# design.net
KiCad netlist of a schematic drawn in Altium Designer
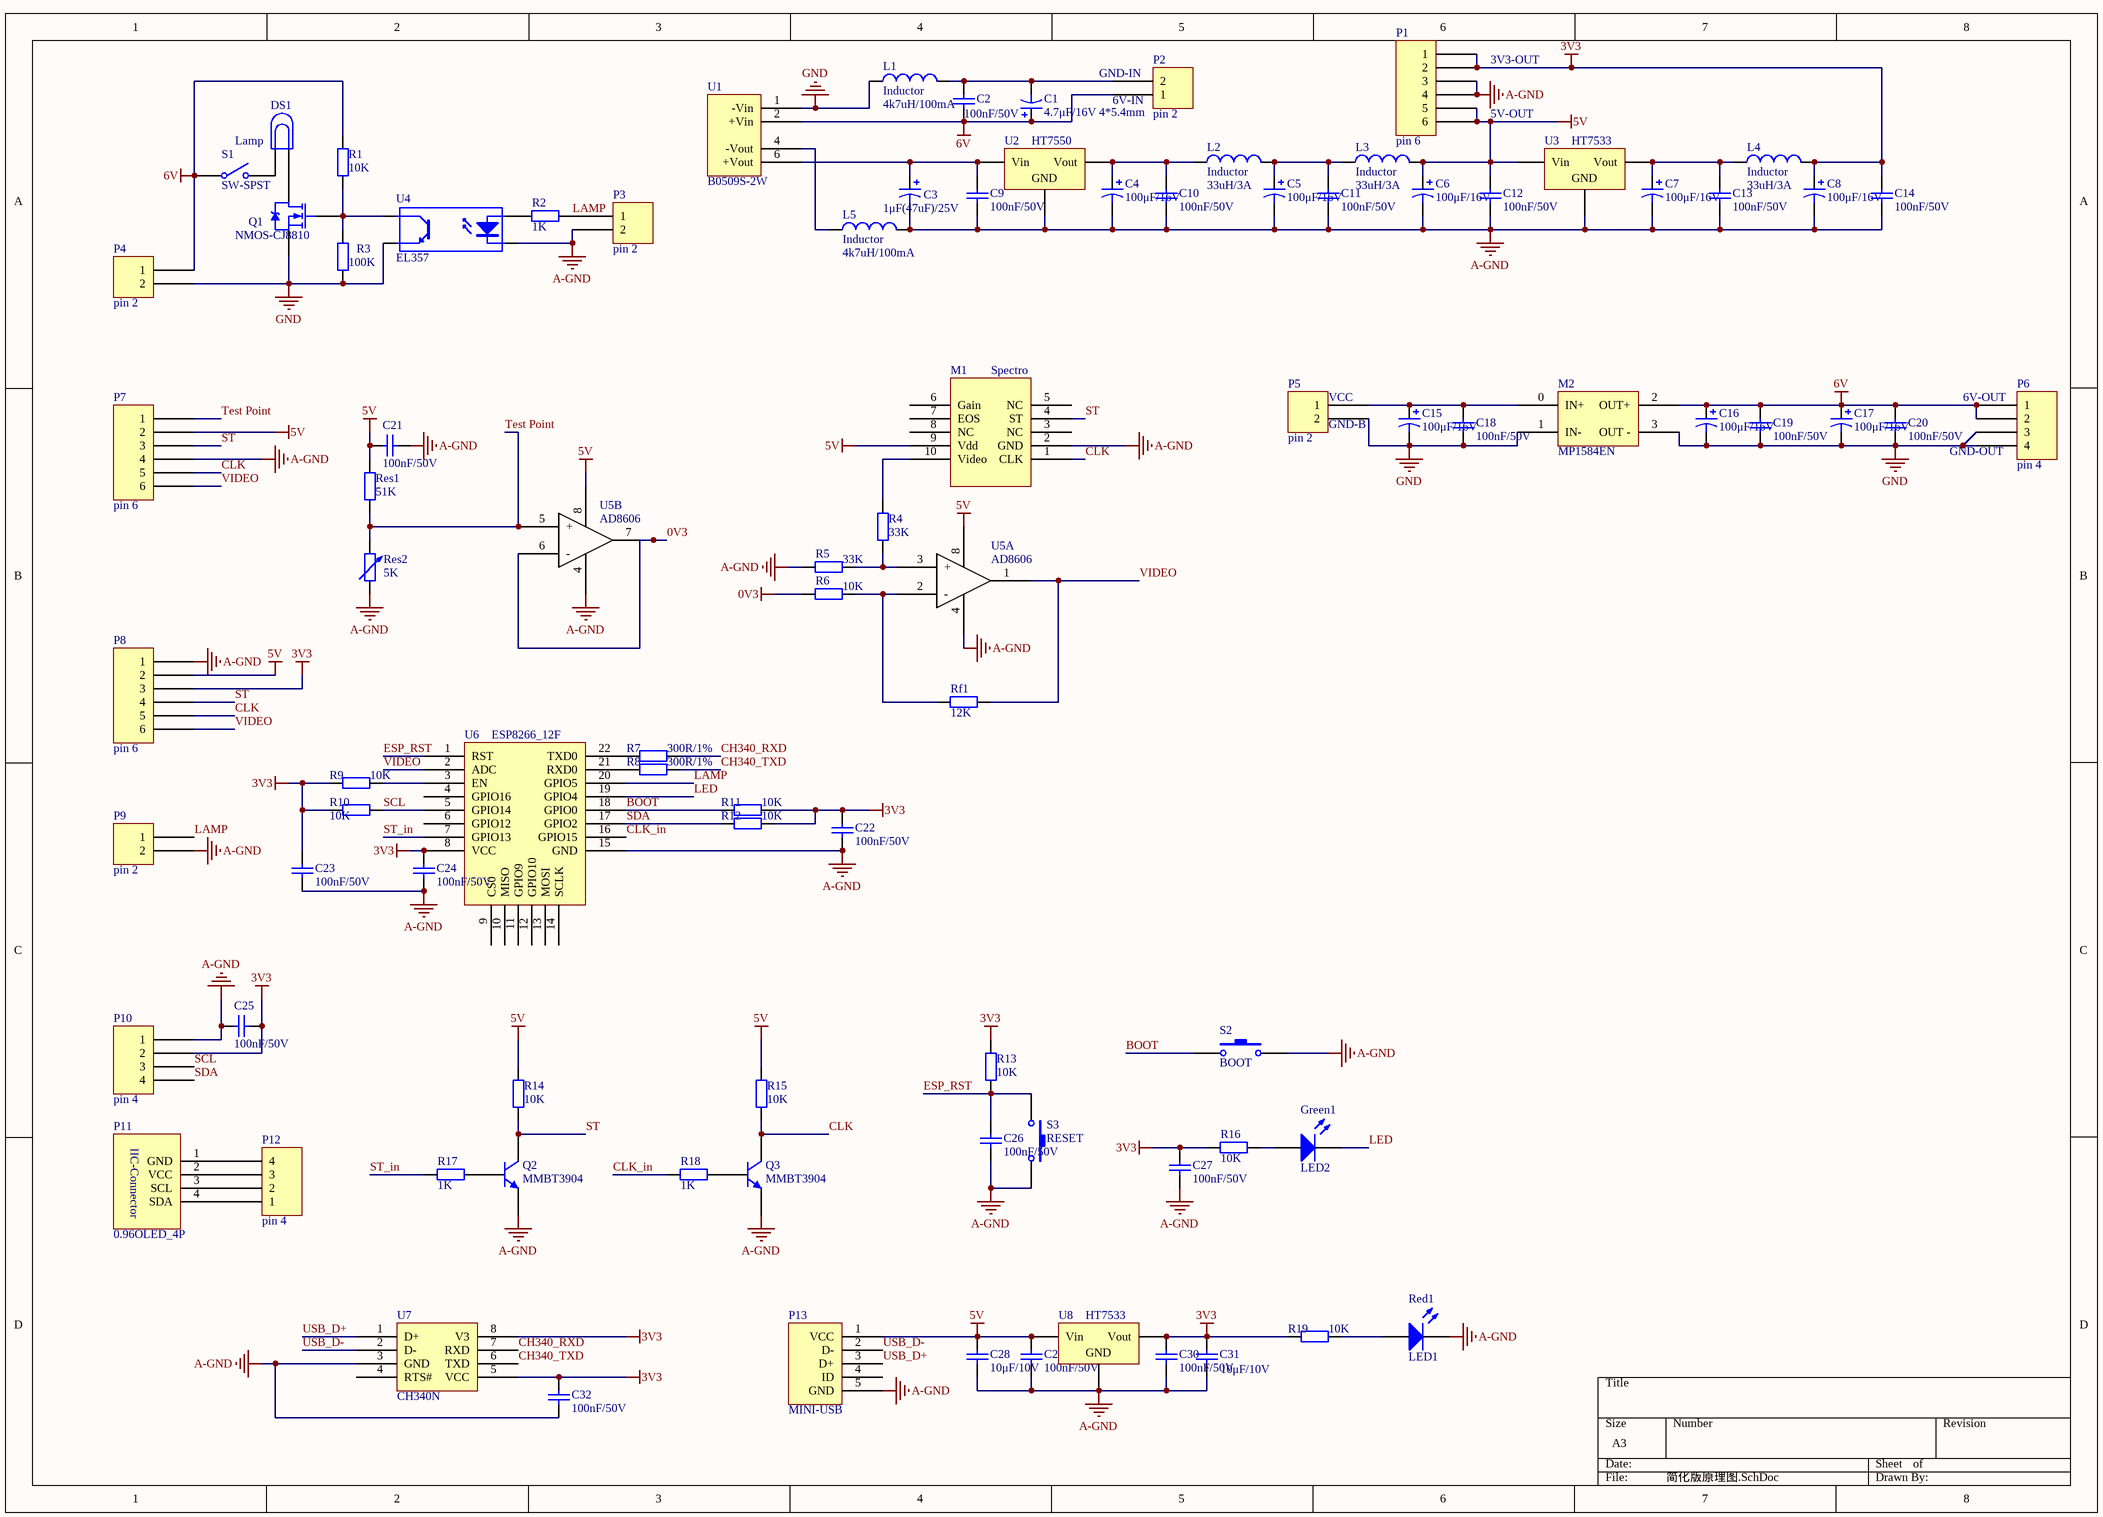
[diagram p0: 简化版原理图.SchDoc]

(export (version "E")
  (design (tool "Eeschema 10.0.6"))
  (components
    (comp (ref "C1")
      (value "4.7μF/16V 4*5.4mm")
      (footprint "CAP4x5.4-SMD")
      (description "Polarized Capacitor (Radial)")
      (fields (field (name "PUBLISHER") "Altium Limited"))
      (libsource (lib "Miscellaneous Devices") (part "Cap Pol1"))
    )
    (comp (ref "C2")
      (value "100nF/50V")
      (footprint "0603")
      (description "Capacitor")
      (fields (field (name "PUBLISHER") "Altium Limited"))
      (libsource (lib "Miscellaneous Devices") (part "Cap"))
    )
    (comp (ref "C3")
      (value "1μF(47uF)/25V")
      (footprint "CAP6.3x5.4-SMD")
      (description "Polarized Capacitor (Radial)")
      (fields (field (name "PUBLISHER") "Altium Limited"))
      (libsource (lib "Miscellaneous Devices") (part "Cap Pol1"))
    )
    (comp (ref "C4")
      (value "100μF/16V")
      (footprint "CAP6.3x5.4-SMD")
      (description "Polarized Capacitor (Radial)")
      (fields (field (name "PUBLISHER") "Altium Limited"))
      (libsource (lib "Miscellaneous Devices") (part "Cap Pol1"))
    )
    (comp (ref "C5")
      (value "100μF/16V")
      (footprint "CAP6.3x5.4-SMD")
      (description "Polarized Capacitor (Radial)")
      (fields (field (name "PUBLISHER") "Altium Limited"))
      (libsource (lib "Miscellaneous Devices") (part "Cap Pol1"))
    )
    (comp (ref "C6")
      (value "100μF/16V")
      (footprint "CAP6.3x5.4-SMD")
      (description "Polarized Capacitor (Radial)")
      (fields (field (name "PUBLISHER") "Altium Limited"))
      (libsource (lib "Miscellaneous Devices") (part "Cap Pol1"))
    )
    (comp (ref "C7")
      (value "100μF/16V")
      (footprint "CAP6.3x5.4-SMD")
      (description "Polarized Capacitor (Radial)")
      (fields (field (name "PUBLISHER") "Altium Limited"))
      (libsource (lib "Miscellaneous Devices") (part "Cap Pol1"))
    )
    (comp (ref "C8")
      (value "100μF/16V")
      (footprint "CAP6.3x5.4-SMD")
      (description "Polarized Capacitor (Radial)")
      (fields (field (name "PUBLISHER") "Altium Limited"))
      (libsource (lib "Miscellaneous Devices") (part "Cap Pol1"))
    )
    (comp (ref "C9")
      (value "100nF/50V")
      (footprint "0603")
      (description "Capacitor")
      (fields (field (name "PUBLISHER") "Altium Limited"))
      (libsource (lib "Miscellaneous Devices") (part "Cap"))
    )
    (comp (ref "C10")
      (value "100nF/50V")
      (footprint "0603")
      (description "Capacitor")
      (fields (field (name "PUBLISHER") "Altium Limited"))
      (libsource (lib "Miscellaneous Devices") (part "Cap"))
    )
    (comp (ref "C11")
      (value "100nF/50V")
      (footprint "0603")
      (description "Capacitor")
      (fields (field (name "PUBLISHER") "Altium Limited"))
      (libsource (lib "Miscellaneous Devices") (part "Cap"))
    )
    (comp (ref "C12")
      (value "100nF/50V")
      (footprint "0603")
      (description "Capacitor")
      (fields (field (name "PUBLISHER") "Altium Limited"))
      (libsource (lib "Miscellaneous Devices") (part "Cap"))
    )
    (comp (ref "C13")
      (value "100nF/50V")
      (footprint "0603")
      (description "Capacitor")
      (fields (field (name "PUBLISHER") "Altium Limited"))
      (libsource (lib "Miscellaneous Devices") (part "Cap"))
    )
    (comp (ref "C14")
      (value "100nF/50V")
      (footprint "0603")
      (description "Capacitor")
      (fields (field (name "PUBLISHER") "Altium Limited"))
      (libsource (lib "Miscellaneous Devices") (part "Cap"))
    )
    (comp (ref "C15")
      (value "100μF/16V")
      (footprint "CAP6.3x5.4-SMD")
      (description "Polarized Capacitor (Radial)")
      (fields (field (name "PUBLISHER") "Altium Limited"))
      (libsource (lib "Miscellaneous Devices") (part "Cap Pol1"))
    )
    (comp (ref "C16")
      (value "100μF/16V")
      (footprint "CAP6.3x5.4-SMD")
      (description "Polarized Capacitor (Radial)")
      (fields (field (name "PUBLISHER") "Altium Limited"))
      (libsource (lib "Miscellaneous Devices") (part "Cap Pol1"))
    )
    (comp (ref "C17")
      (value "100μF/16V")
      (footprint "CAP6.3x5.4-SMD")
      (description "Polarized Capacitor (Radial)")
      (fields (field (name "PUBLISHER") "Altium Limited"))
      (libsource (lib "Miscellaneous Devices") (part "Cap Pol1"))
    )
    (comp (ref "C18")
      (value "100nF/50V")
      (footprint "0603")
      (description "Capacitor")
      (fields (field (name "PUBLISHER") "Altium Limited"))
      (libsource (lib "Miscellaneous Devices") (part "Cap"))
    )
    (comp (ref "C19")
      (value "100nF/50V")
      (footprint "0603")
      (description "Capacitor")
      (fields (field (name "PUBLISHER") "Altium Limited"))
      (libsource (lib "Miscellaneous Devices") (part "Cap"))
    )
    (comp (ref "C20")
      (value "100nF/50V")
      (footprint "0603")
      (description "Capacitor")
      (fields (field (name "PUBLISHER") "Altium Limited"))
      (libsource (lib "Miscellaneous Devices") (part "Cap"))
    )
    (comp (ref "C21")
      (value "100nF/50V")
      (footprint "0603")
      (description "Capacitor")
      (fields (field (name "PUBLISHER") "Altium Limited"))
      (libsource (lib "Miscellaneous Devices") (part "Cap"))
    )
    (comp (ref "C22")
      (value "100nF/50V")
      (footprint "0603")
      (description "Capacitor")
      (fields (field (name "PUBLISHER") "Altium Limited"))
      (libsource (lib "Miscellaneous Devices") (part "Cap"))
    )
    (comp (ref "C23")
      (value "100nF/50V")
      (footprint "0603")
      (description "Capacitor")
      (fields (field (name "PUBLISHER") "Altium Limited"))
      (libsource (lib "Miscellaneous Devices") (part "Cap"))
    )
    (comp (ref "C24")
      (value "100nF/50V")
      (footprint "0603")
      (description "Capacitor")
      (fields (field (name "PUBLISHER") "Altium Limited"))
      (libsource (lib "Miscellaneous Devices") (part "Cap"))
    )
    (comp (ref "C25")
      (value "100nF/50V")
      (footprint "0603")
      (description "Capacitor")
      (fields (field (name "PUBLISHER") "Altium Limited"))
      (libsource (lib "Miscellaneous Devices") (part "Cap"))
    )
    (comp (ref "C26")
      (value "100nF/50V")
      (footprint "0603")
      (description "Capacitor")
      (fields (field (name "PUBLISHER") "Altium Limited"))
      (libsource (lib "Miscellaneous Devices") (part "Cap"))
    )
    (comp (ref "C27")
      (value "100nF/50V")
      (footprint "0603")
      (description "Capacitor")
      (fields (field (name "PUBLISHER") "Altium Limited"))
      (libsource (lib "Miscellaneous Devices") (part "Cap"))
    )
    (comp (ref "C28")
      (value "10μF/10V")
      (footprint "0805")
      (description "Capacitor")
      (fields (field (name "PUBLISHER") "Altium Limited"))
      (libsource (lib "Miscellaneous Devices") (part "Cap"))
    )
    (comp (ref "C29")
      (value "100nF/50V")
      (footprint "0603")
      (description "Capacitor")
      (fields (field (name "PUBLISHER") "Altium Limited"))
      (libsource (lib "Miscellaneous Devices") (part "Cap"))
    )
    (comp (ref "C30")
      (value "100nF/50V")
      (footprint "0603")
      (description "Capacitor")
      (fields (field (name "PUBLISHER") "Altium Limited"))
      (libsource (lib "Miscellaneous Devices") (part "Cap"))
    )
    (comp (ref "C31")
      (value "10μF/10V")
      (footprint "0805")
      (description "Capacitor")
      (fields (field (name "PUBLISHER") "Altium Limited"))
      (libsource (lib "Miscellaneous Devices") (part "Cap"))
    )
    (comp (ref "C32")
      (value "100nF/50V")
      (footprint "0603")
      (description "Capacitor")
      (fields (field (name "PUBLISHER") "Altium Limited"))
      (libsource (lib "Miscellaneous Devices") (part "Cap"))
    )
    (comp (ref "DS1")
      (value "Lamp")
      (footprint "LAMP")
      (description "Incandescent Bulb")
      (fields (field (name "PUBLISHER") "Altium Limited"))
      (libsource (lib "Miscellaneous Devices") (part "Lamp"))
    )
    (comp (ref "Green1")
      (value "LED2")
      (footprint "0805-LED")
      (description "Typical RED GaAs LED")
      (fields (field (name "PUBLISHER") "Altium Limited"))
      (libsource (lib "Miscellaneous Devices") (part "LED1"))
    )
    (comp (ref "L1")
      (value "Inductor")
      (footprint "L 0810")
      (fields (field (name "ALTIUM_VALUE") "4k7uH/100mA") (field (name "PUBLISHER") "Altium Limited"))
      (libsource (lib "Miscellaneous Devices") (part "Inductor"))
    )
    (comp (ref "L2")
      (value "Inductor")
      (footprint "0650")
      (fields (field (name "ALTIUM_VALUE") "33uH/3A") (field (name "PUBLISHER") "Altium Limited"))
      (libsource (lib "Miscellaneous Devices") (part "Inductor"))
    )
    (comp (ref "L3")
      (value "Inductor")
      (footprint "0650")
      (fields (field (name "ALTIUM_VALUE") "33uH/3A") (field (name "PUBLISHER") "Altium Limited"))
      (libsource (lib "Miscellaneous Devices") (part "Inductor"))
    )
    (comp (ref "L4")
      (value "Inductor")
      (footprint "0650")
      (fields (field (name "ALTIUM_VALUE") "33uH/3A") (field (name "PUBLISHER") "Altium Limited"))
      (libsource (lib "Miscellaneous Devices") (part "Inductor"))
    )
    (comp (ref "L5")
      (value "Inductor")
      (footprint "L 0810")
      (fields (field (name "ALTIUM_VALUE") "4k7uH/100mA") (field (name "PUBLISHER") "Altium Limited"))
      (libsource (lib "Miscellaneous Devices") (part "Inductor"))
    )
    (comp (ref "M1") (value "Spectro") (footprint "c10988ma") (libsource (lib "第一版SCH库") (part "Spectro")))
    (comp (ref "M2")
      (value "MP1584EN")
      (footprint "MP1584EN模块")
      (libsource (lib "简化版PCB") (part "MP1584EN模块"))
    )
    (comp (ref "P1") (value "pin 6") (footprint "PIN-6-2.54-1.0") (libsource (lib "简化版PCB") (part "pin 6")))
    (comp (ref "P2") (value "pin 2") (footprint "PIN-2-2.54-1.0") (libsource (lib "") (part "pin 2_2")))
    (comp (ref "P3") (value "pin 2") (footprint "PIN-2-2.54-1.0") (libsource (lib "简化版PCB") (part "pin 2")))
    (comp (ref "P4") (value "pin 2") (footprint "PIN-2-2.54-1.0") (libsource (lib "") (part "pin 2_1")))
    (comp (ref "P5") (value "pin 2") (footprint "PIN-2-2.54-1.0") (libsource (lib "") (part "pin 2_1")))
    (comp (ref "P6") (value "pin 4") (footprint "PIN-4-2.54-1.0") (libsource (lib "") (part "pin 4_2")))
    (comp (ref "P7") (value "pin 6") (footprint "PIN-6-2.54-1.0") (libsource (lib "简化版PCB") (part "pin 6")))
    (comp (ref "P8") (value "pin 6") (footprint "PIN-6-2.54-1.0") (libsource (lib "简化版PCB") (part "pin 6")))
    (comp (ref "P9") (value "pin 2") (footprint "PIN-2-2.54-1.0") (libsource (lib "") (part "pin 2_1")))
    (comp (ref "P10") (value "pin 4") (footprint "PIN-4-2.54-1.0") (libsource (lib "") (part "pin 4_1")))
    (comp (ref "P11")
      (value "0.96OLED_4P")
      (footprint "OLED0.96-4P")
      (libsource (lib "第一版SCH库") (part "0.96OLED_4P"))
    )
    (comp (ref "P12") (value "pin 4") (footprint "PIN-4-2.54-1.0") (libsource (lib "简化版PCB") (part "pin 4")))
    (comp (ref "P13")
      (value "MINI-USB")
      (footprint "Micro_USB全贴片")
      (libsource (lib "第一版SCH库") (part "MINI-USB_JX"))
    )
    (comp (ref "Q1")
      (value "NMOS-CJ8810")
      (footprint "SOT-23")
      (description "N-Channel Power MOSFET")
      (fields (field (name "PUBLISHER") "Altium Limited"))
      (libsource (lib "简化版PCB") (part "NMOS-2"))
    )
    (comp (ref "Q2")
      (value "MMBT3904")
      (footprint "SOT-23")
      (description "NPN General Purpose Amplifier")
      (fields (field (name "PUBLISHER") "Altium Limited"))
      (libsource (lib "简化版PCB") (part "2N3904"))
    )
    (comp (ref "Q3")
      (value "MMBT3904")
      (footprint "SOT-23")
      (description "NPN General Purpose Amplifier")
      (fields (field (name "PUBLISHER") "Altium Limited"))
      (libsource (lib "简化版PCB") (part "2N3904"))
    )
    (comp (ref "R1")
      (value "10K")
      (footprint "0603")
      (description "Resistor")
      (fields (field (name "PUBLISHER") "Altium Limited"))
      (libsource (lib "") (part "Res2_1"))
    )
    (comp (ref "R2")
      (value "1K")
      (footprint "0603")
      (description "Resistor")
      (fields (field (name "PUBLISHER") "Altium Limited"))
      (libsource (lib "Miscellaneous Devices") (part "Res2"))
    )
    (comp (ref "R3")
      (value "100K")
      (footprint "0603")
      (description "Resistor")
      (fields (field (name "PUBLISHER") "Altium Limited"))
      (libsource (lib "") (part "Res2_1"))
    )
    (comp (ref "R4")
      (value "33K")
      (footprint "0603")
      (description "Resistor")
      (fields (field (name "PUBLISHER") "Altium Limited"))
      (libsource (lib "") (part "Res2_1"))
    )
    (comp (ref "R5")
      (value "33K")
      (footprint "0603")
      (description "Resistor")
      (fields (field (name "PUBLISHER") "Altium Limited"))
      (libsource (lib "Miscellaneous Devices") (part "Res2"))
    )
    (comp (ref "R6")
      (value "10K")
      (footprint "0603")
      (description "Resistor")
      (fields (field (name "PUBLISHER") "Altium Limited"))
      (libsource (lib "Miscellaneous Devices") (part "Res2"))
    )
    (comp (ref "R7")
      (value "300R/1%")
      (footprint "0603")
      (description "Resistor")
      (fields (field (name "PUBLISHER") "Altium Limited"))
      (libsource (lib "Miscellaneous Devices") (part "Res2"))
    )
    (comp (ref "R8")
      (value "300R/1%")
      (footprint "0603")
      (description "Resistor")
      (fields (field (name "PUBLISHER") "Altium Limited"))
      (libsource (lib "Miscellaneous Devices") (part "Res2"))
    )
    (comp (ref "R9")
      (value "10K")
      (footprint "0603")
      (description "Resistor")
      (fields (field (name "PUBLISHER") "Altium Limited"))
      (libsource (lib "Miscellaneous Devices") (part "Res2"))
    )
    (comp (ref "R10")
      (value "10K")
      (footprint "0603")
      (description "Resistor")
      (fields (field (name "PUBLISHER") "Altium Limited"))
      (libsource (lib "Miscellaneous Devices") (part "Res2"))
    )
    (comp (ref "R11")
      (value "10K")
      (footprint "0603")
      (description "Resistor")
      (fields (field (name "PUBLISHER") "Altium Limited"))
      (libsource (lib "Miscellaneous Devices") (part "Res2"))
    )
    (comp (ref "R12")
      (value "10K")
      (footprint "0603")
      (description "Resistor")
      (fields (field (name "PUBLISHER") "Altium Limited"))
      (libsource (lib "Miscellaneous Devices") (part "Res2"))
    )
    (comp (ref "R13")
      (value "10K")
      (footprint "0603")
      (description "Resistor")
      (fields (field (name "PUBLISHER") "Altium Limited"))
      (libsource (lib "") (part "Res2_1"))
    )
    (comp (ref "R14")
      (value "10K")
      (footprint "0603")
      (description "Resistor")
      (fields (field (name "PUBLISHER") "Altium Limited"))
      (libsource (lib "") (part "Res2_1"))
    )
    (comp (ref "R15")
      (value "10K")
      (footprint "0603")
      (description "Resistor")
      (fields (field (name "PUBLISHER") "Altium Limited"))
      (libsource (lib "") (part "Res2_1"))
    )
    (comp (ref "R16")
      (value "10K")
      (footprint "0603")
      (description "Resistor")
      (fields (field (name "PUBLISHER") "Altium Limited"))
      (libsource (lib "") (part "Res2_2"))
    )
    (comp (ref "R17")
      (value "1K")
      (footprint "0603")
      (description "Resistor")
      (fields (field (name "PUBLISHER") "Altium Limited"))
      (libsource (lib "") (part "Res2_2"))
    )
    (comp (ref "R18")
      (value "1K")
      (footprint "0603")
      (description "Resistor")
      (fields (field (name "PUBLISHER") "Altium Limited"))
      (libsource (lib "") (part "Res2_2"))
    )
    (comp (ref "R19")
      (value "10K")
      (footprint "0603")
      (description "Resistor")
      (fields (field (name "PUBLISHER") "Altium Limited"))
      (libsource (lib "Miscellaneous Devices") (part "Res2"))
    )
    (comp (ref "Red1")
      (value "LED1")
      (footprint "0805-LED")
      (description "Typical RED GaAs LED")
      (fields (field (name "PUBLISHER") "Altium Limited"))
      (libsource (lib "Miscellaneous Devices") (part "LED1"))
    )
    (comp (ref "Res1")
      (value "51K")
      (footprint "0603")
      (description "Resistor")
      (fields (field (name "PUBLISHER") "Altium Limited"))
      (libsource (lib "") (part "Res2_1"))
    )
    (comp (ref "Res2")
      (value "5K")
      (footprint "RES-ADJ")
      (description "Variable Resistor")
      (fields (field (name "PUBLISHER") "Altium Limited"))
      (libsource (lib "Miscellaneous Devices") (part "Res Adj2"))
    )
    (comp (ref "Rf1")
      (value "12K")
      (footprint "0603")
      (description "Resistor")
      (fields (field (name "PUBLISHER") "Altium Limited"))
      (libsource (lib "Miscellaneous Devices") (part "Res2"))
    )
    (comp (ref "S1")
      (value "SW-SPST")
      (footprint "swich-big")
      (description "Single-Pole, Single-Throw Switch")
      (fields (field (name "PUBLISHER") "Altium Limited"))
      (libsource (lib "Miscellaneous Devices") (part "SW-SPST"))
    )
    (comp (ref "S2")
      (value "BOOT")
      (footprint "Swich-mini")
      (description "Switch")
      (fields (field (name "PUBLISHER") "Altium Limited"))
      (libsource (lib "Miscellaneous Devices") (part "SW-PB"))
    )
    (comp (ref "S3")
      (value "RESET")
      (footprint "Swich-mini")
      (description "Switch")
      (fields (field (name "PUBLISHER") "Altium Limited"))
      (libsource (lib "Miscellaneous Devices") (part "SW-PB"))
    )
    (comp (ref "U1")
      (value "B0509S-2W")
      (footprint "B0509S-2W")
      (libsource (lib "第一版SCH库") (part "B0509S-2W"))
    )
    (comp (ref "U2")
      (value "HT7550")
      (footprint "SOT-89")
      (description "Voltage Regulator")
      (fields (field (name "PUBLISHER") "Altium Limited"))
      (libsource (lib "简化版PCB") (part "Volt Reg"))
    )
    (comp (ref "U3")
      (value "HT7533")
      (footprint "SOT-89")
      (description "Voltage Regulator")
      (fields (field (name "PUBLISHER") "Altium Limited"))
      (libsource (lib "简化版PCB") (part "Volt Reg"))
    )
    (comp (ref "U4")
      (value "EL357")
      (footprint "SOP4-bigger")
      (description "4-Pin Phototransistor Optocoupler")
      (fields (field (name "PUBLISHER") "Altium Limited"))
      (libsource (lib "Miscellaneous Devices") (part "Optoisolator1"))
    )
    (comp (ref "U5") (value "AD8606") (footprint "SOP8") (libsource (lib "第一版SCH库") (part "LM358")))
    (comp (ref "U6")
      (value "ESP8266_12F")
      (footprint "esp8266-12f")
      (libsource (lib "第一版SCH库") (part "ESP8266_12F"))
    )
    (comp (ref "U7") (value "CH340N") (footprint "SOP8") (libsource (lib "简化版PCB") (part "CH340N")))
    (comp (ref "U8")
      (value "HT7533")
      (footprint "SOT-89")
      (description "Voltage Regulator")
      (fields (field (name "PUBLISHER") "Altium Limited"))
      (libsource (lib "简化版PCB") (part "Volt Reg"))
    )
  )
  (nets
    (net (code "1") (name "/BOOT") (class "Default")
      (node (ref "R11") (pin "1") (pinfunction "1_1") (pintype "passive"))
      (node (ref "S2") (pin "1") (pinfunction "1_1") (pintype "passive"))
      (node (ref "U6") (pin "18") (pinfunction "GPIO0_18") (pintype "passive"))
    )
    (net (code "2") (name "/CH340_RXD") (class "Default")
      (node (ref "R7") (pin "2") (pinfunction "2_2") (pintype "passive"))
      (node (ref "U7") (pin "7") (pinfunction "RXD_7") (pintype "passive"))
    )
    (net (code "3") (name "/CH340_TXD") (class "Default")
      (node (ref "R8") (pin "2") (pinfunction "2_2") (pintype "passive"))
      (node (ref "U7") (pin "6") (pinfunction "TXD_6") (pintype "passive"))
    )
    (net (code "4") (name "/CLK") (class "Default")
      (node (ref "M1") (pin "1") (pinfunction "CLK_1") (pintype "passive"))
      (node (ref "P7") (pin "5") (pinfunction "5_5") (pintype "passive"))
      (node (ref "P8") (pin "5") (pinfunction "5_5") (pintype "passive"))
      (node (ref "Q3") (pin "3") (pinfunction "C_3") (pintype "passive"))
      (node (ref "R15") (pin "1") (pinfunction "1_1") (pintype "passive"))
    )
    (net (code "5") (name "/CLK_in") (class "Default")
      (node (ref "R18") (pin "2") (pinfunction "2_2") (pintype "passive"))
      (node (ref "U6") (pin "16") (pinfunction "GPIO15_16") (pintype "passive"))
    )
    (net (code "6") (name "/ESP_RST") (class "Default")
      (node (ref "C26") (pin "2") (pinfunction "2_2") (pintype "passive"))
      (node (ref "R13") (pin "1") (pinfunction "1_1") (pintype "passive"))
      (node (ref "S3") (pin "1") (pinfunction "1_1") (pintype "passive"))
      (node (ref "U6") (pin "1") (pinfunction "RST_1") (pintype "passive"))
    )
    (net (code "7") (name "/LAMP") (class "Default")
      (node (ref "P3") (pin "1") (pinfunction "1_1") (pintype "passive"))
      (node (ref "P9") (pin "1") (pinfunction "1_1") (pintype "passive"))
      (node (ref "R2") (pin "2") (pinfunction "2_2") (pintype "passive"))
      (node (ref "U6") (pin "20") (pinfunction "GPIO5_20") (pintype "passive"))
    )
    (net (code "8") (name "/LED") (class "Default")
      (node (ref "Green1") (pin "2") (pinfunction "K_2") (pintype "passive"))
      (node (ref "U6") (pin "19") (pinfunction "GPIO4_19") (pintype "passive"))
    )
    (net (code "9") (name "/SCL") (class "Default")
      (node (ref "P10") (pin "3") (pinfunction "3_3") (pintype "passive"))
      (node (ref "R10") (pin "2") (pinfunction "2_2") (pintype "passive"))
      (node (ref "U6") (pin "5") (pinfunction "GPIO14_5") (pintype "passive"))
    )
    (net (code "10") (name "/SDA") (class "Default")
      (node (ref "P10") (pin "4") (pinfunction "4_4") (pintype "passive"))
      (node (ref "R12") (pin "1") (pinfunction "1_1") (pintype "passive"))
      (node (ref "U6") (pin "17") (pinfunction "GPIO2_17") (pintype "passive"))
    )
    (net (code "11") (name "/ST") (class "Default")
      (node (ref "M1") (pin "4") (pinfunction "ST_4") (pintype "passive"))
      (node (ref "P7") (pin "3") (pinfunction "3_3") (pintype "passive"))
      (node (ref "P8") (pin "4") (pinfunction "4_4") (pintype "passive"))
      (node (ref "Q2") (pin "3") (pinfunction "C_3") (pintype "passive"))
      (node (ref "R14") (pin "1") (pinfunction "1_1") (pintype "passive"))
    )
    (net (code "12") (name "/ST_in") (class "Default")
      (node (ref "R17") (pin "2") (pinfunction "2_2") (pintype "passive"))
      (node (ref "U6") (pin "7") (pinfunction "GPIO13_7") (pintype "passive"))
    )
    (net (code "13") (name "/Test Point") (class "Default")
      (node (ref "P7") (pin "1") (pinfunction "1_1") (pintype "passive"))
      (node (ref "Res1") (pin "1") (pinfunction "1_1") (pintype "passive"))
      (node (ref "Res2") (pin "2") (pinfunction "2_2") (pintype "passive"))
      (node (ref "U5") (pin "5") (pinfunction "+_5") (pintype "passive"))
    )
    (net (code "14") (name "/USB_D+") (class "Default")
      (node (ref "P13") (pin "3") (pinfunction "D+_3") (pintype "passive"))
      (node (ref "U7") (pin "1") (pinfunction "D+_1") (pintype "passive"))
    )
    (net (code "15") (name "/USB_D-") (class "Default")
      (node (ref "P13") (pin "2") (pinfunction "D-_2") (pintype "passive"))
      (node (ref "U7") (pin "2") (pinfunction "D-_2") (pintype "passive"))
    )
    (net (code "16") (name "/VIDEO") (class "Default")
      (node (ref "P7") (pin "6") (pinfunction "6_6") (pintype "passive"))
      (node (ref "P8") (pin "6") (pinfunction "6_6") (pintype "passive"))
      (node (ref "Rf1") (pin "2") (pinfunction "2_2") (pintype "passive"))
      (node (ref "U5") (pin "1") (pinfunction "OUT_1") (pintype "passive"))
      (node (ref "U6") (pin "2") (pinfunction "ADC_2") (pintype "passive"))
    )
    (net (code "17") (name "0V3") (class "Default")
      (node (ref "R6") (pin "1") (pinfunction "1_1") (pintype "passive"))
      (node (ref "U5") (pin "6") (pinfunction "-_6") (pintype "passive"))
      (node (ref "U5") (pin "7") (pinfunction "OUT_7") (pintype "passive"))
    )
    (net (code "18") (name "3V3") (class "Default")
      (node (ref "C14") (pin "2") (pinfunction "2_2") (pintype "passive"))
      (node (ref "C22") (pin "2") (pinfunction "2_2") (pintype "passive"))
      (node (ref "C23") (pin "2") (pinfunction "2_2") (pintype "passive"))
      (node (ref "C24") (pin "2") (pinfunction "2_2") (pintype "passive"))
      (node (ref "C25") (pin "1") (pinfunction "1_1") (pintype "passive"))
      (node (ref "C27") (pin "2") (pinfunction "2_2") (pintype "passive"))
      (node (ref "C30") (pin "2") (pinfunction "2_2") (pintype "passive"))
      (node (ref "C31") (pin "1") (pinfunction "1_1") (pintype "passive"))
      (node (ref "C32") (pin "2") (pinfunction "2_2") (pintype "passive"))
      (node (ref "C8") (pin "1") (pinfunction "1_1") (pintype "passive"))
      (node (ref "L4") (pin "2") (pinfunction "2_2") (pintype "passive"))
      (node (ref "P1") (pin "1") (pinfunction "1_1") (pintype "passive"))
      (node (ref "P1") (pin "2") (pinfunction "2_2") (pintype "passive"))
      (node (ref "P10") (pin "2") (pinfunction "2_2") (pintype "passive"))
      (node (ref "P8") (pin "3") (pinfunction "3_3") (pintype "passive"))
      (node (ref "R10") (pin "1") (pinfunction "1_1") (pintype "passive"))
      (node (ref "R11") (pin "2") (pinfunction "2_2") (pintype "passive"))
      (node (ref "R12") (pin "2") (pinfunction "2_2") (pintype "passive"))
      (node (ref "R13") (pin "2") (pinfunction "2_2") (pintype "passive"))
      (node (ref "R16") (pin "2") (pinfunction "2_2") (pintype "passive"))
      (node (ref "R19") (pin "1") (pinfunction "1_1") (pintype "passive"))
      (node (ref "R9") (pin "1") (pinfunction "1_1") (pintype "passive"))
      (node (ref "U6") (pin "8") (pinfunction "VCC_8") (pintype "passive"))
      (node (ref "U7") (pin "5") (pinfunction "VCC_5") (pintype "passive"))
      (node (ref "U7") (pin "8") (pinfunction "V3_8") (pintype "passive"))
      (node (ref "U8") (pin "3") (pinfunction "Vout_3") (pintype "passive"))
    )
    (net (code "19") (name "5V") (class "Default")
      (node (ref "C12") (pin "2") (pinfunction "2_2") (pintype "passive"))
      (node (ref "C21") (pin "2") (pinfunction "2_2") (pintype "passive"))
      (node (ref "C28") (pin "1") (pinfunction "1_1") (pintype "passive"))
      (node (ref "C29") (pin "2") (pinfunction "2_2") (pintype "passive"))
      (node (ref "C6") (pin "1") (pinfunction "1_1") (pintype "passive"))
      (node (ref "L3") (pin "2") (pinfunction "2_2") (pintype "passive"))
      (node (ref "M1") (pin "9") (pinfunction "Vdd_9") (pintype "passive"))
      (node (ref "P1") (pin "5") (pinfunction "5_5") (pintype "passive"))
      (node (ref "P1") (pin "6") (pinfunction "6_6") (pintype "passive"))
      (node (ref "P13") (pin "1") (pinfunction "VCC_1") (pintype "passive"))
      (node (ref "P7") (pin "2") (pinfunction "2_2") (pintype "passive"))
      (node (ref "P8") (pin "2") (pinfunction "2_2") (pintype "passive"))
      (node (ref "R14") (pin "2") (pinfunction "2_2") (pintype "passive"))
      (node (ref "R15") (pin "2") (pinfunction "2_2") (pintype "passive"))
      (node (ref "Res1") (pin "2") (pinfunction "2_2") (pintype "passive"))
      (node (ref "U3") (pin "2") (pinfunction "Vin_2") (pintype "passive"))
      (node (ref "U5") (pin "8") (pinfunction "VCC_8") (pintype "passive"))
      (node (ref "U8") (pin "2") (pinfunction "Vin_2") (pintype "passive"))
    )
    (net (code "20") (name "6V") (class "Default")
      (node (ref "C1") (pin "1") (pinfunction "1_1") (pintype "passive"))
      (node (ref "C16") (pin "1") (pinfunction "1_1") (pintype "passive"))
      (node (ref "C17") (pin "1") (pinfunction "1_1") (pintype "passive"))
      (node (ref "C19") (pin "2") (pinfunction "2_2") (pintype "passive"))
      (node (ref "C2") (pin "1") (pinfunction "1_1") (pintype "passive"))
      (node (ref "C20") (pin "2") (pinfunction "2_2") (pintype "passive"))
      (node (ref "M2") (pin "2") (pinfunction "OUT+_2") (pintype "passive"))
      (node (ref "P2") (pin "1") (pinfunction "1_1") (pintype "passive"))
      (node (ref "P4") (pin "1") (pinfunction "1_1") (pintype "passive"))
      (node (ref "P6") (pin "1") (pinfunction "1_1") (pintype "passive"))
      (node (ref "P6") (pin "2") (pinfunction "2_2") (pintype "passive"))
      (node (ref "R1") (pin "2") (pinfunction "2_2") (pintype "passive"))
      (node (ref "S1") (pin "1") (pinfunction "COMMON_1") (pintype "passive"))
      (node (ref "U1") (pin "2") (pinfunction "+Vin_2") (pintype "passive"))
    )
    (net (code "21") (name "A-GND") (class "Default")
      (node (ref "C10") (pin "1") (pinfunction "1_1") (pintype "passive"))
      (node (ref "C11") (pin "1") (pinfunction "1_1") (pintype "passive"))
      (node (ref "C12") (pin "1") (pinfunction "1_1") (pintype "passive"))
      (node (ref "C13") (pin "1") (pinfunction "1_1") (pintype "passive"))
      (node (ref "C14") (pin "1") (pinfunction "1_1") (pintype "passive"))
      (node (ref "C21") (pin "1") (pinfunction "1_1") (pintype "passive"))
      (node (ref "C22") (pin "1") (pinfunction "1_1") (pintype "passive"))
      (node (ref "C23") (pin "1") (pinfunction "1_1") (pintype "passive"))
      (node (ref "C24") (pin "1") (pinfunction "1_1") (pintype "passive"))
      (node (ref "C25") (pin "2") (pinfunction "2_2") (pintype "passive"))
      (node (ref "C26") (pin "1") (pinfunction "1_1") (pintype "passive"))
      (node (ref "C27") (pin "1") (pinfunction "1_1") (pintype "passive"))
      (node (ref "C28") (pin "2") (pinfunction "2_2") (pintype "passive"))
      (node (ref "C29") (pin "1") (pinfunction "1_1") (pintype "passive"))
      (node (ref "C3") (pin "2") (pinfunction "2_2") (pintype "passive"))
      (node (ref "C30") (pin "1") (pinfunction "1_1") (pintype "passive"))
      (node (ref "C31") (pin "2") (pinfunction "2_2") (pintype "passive"))
      (node (ref "C32") (pin "1") (pinfunction "1_1") (pintype "passive"))
      (node (ref "C4") (pin "2") (pinfunction "2_2") (pintype "passive"))
      (node (ref "C5") (pin "2") (pinfunction "2_2") (pintype "passive"))
      (node (ref "C6") (pin "2") (pinfunction "2_2") (pintype "passive"))
      (node (ref "C7") (pin "2") (pinfunction "2_2") (pintype "passive"))
      (node (ref "C8") (pin "2") (pinfunction "2_2") (pintype "passive"))
      (node (ref "C9") (pin "1") (pinfunction "1_1") (pintype "passive"))
      (node (ref "L5") (pin "2") (pinfunction "2_2") (pintype "passive"))
      (node (ref "M1") (pin "2") (pinfunction "GND_2") (pintype "passive"))
      (node (ref "P1") (pin "3") (pinfunction "3_3") (pintype "passive"))
      (node (ref "P1") (pin "4") (pinfunction "4_4") (pintype "passive"))
      (node (ref "P10") (pin "1") (pinfunction "1_1") (pintype "passive"))
      (node (ref "P13") (pin "5") (pinfunction "GND_5") (pintype "passive"))
      (node (ref "P3") (pin "2") (pinfunction "2_2") (pintype "passive"))
      (node (ref "P7") (pin "4") (pinfunction "4_4") (pintype "passive"))
      (node (ref "P8") (pin "1") (pinfunction "1_1") (pintype "passive"))
      (node (ref "P9") (pin "2") (pinfunction "2_2") (pintype "passive"))
      (node (ref "Q2") (pin "2") (pinfunction "E_2") (pintype "passive"))
      (node (ref "Q3") (pin "2") (pinfunction "E_2") (pintype "passive"))
      (node (ref "R5") (pin "1") (pinfunction "1_1") (pintype "passive"))
      (node (ref "Red1") (pin "2") (pinfunction "K_2") (pintype "passive"))
      (node (ref "Res2") (pin "1") (pinfunction "1_1") (pintype "passive"))
      (node (ref "S2") (pin "2") (pinfunction "2_2") (pintype "passive"))
      (node (ref "S3") (pin "2") (pinfunction "2_2") (pintype "passive"))
      (node (ref "U2") (pin "1") (pinfunction "GND_1") (pintype "passive"))
      (node (ref "U3") (pin "1") (pinfunction "GND_1") (pintype "passive"))
      (node (ref "U4") (pin "2") (pinfunction "K_2") (pintype "passive"))
      (node (ref "U5") (pin "4") (pinfunction "VEE_4") (pintype "passive"))
      (node (ref "U6") (pin "15") (pinfunction "GND_15") (pintype "passive"))
      (node (ref "U7") (pin "3") (pinfunction "GND_3") (pintype "passive"))
      (node (ref "U8") (pin "1") (pinfunction "GND_1") (pintype "passive"))
    )
    (net (code "22") (name "GND") (class "Default")
      (node (ref "C15") (pin "2") (pinfunction "2_2") (pintype "passive"))
      (node (ref "C16") (pin "2") (pinfunction "2_2") (pintype "passive"))
      (node (ref "C17") (pin "2") (pinfunction "2_2") (pintype "passive"))
      (node (ref "C18") (pin "1") (pinfunction "1_1") (pintype "passive"))
      (node (ref "C19") (pin "1") (pinfunction "1_1") (pintype "passive"))
      (node (ref "C20") (pin "1") (pinfunction "1_1") (pintype "passive"))
      (node (ref "L1") (pin "1") (pinfunction "1_1") (pintype "passive"))
      (node (ref "M2") (pin "1") (pinfunction "IN-_1") (pintype "passive"))
      (node (ref "M2") (pin "3") (pinfunction "OUT_-_3") (pintype "passive"))
      (node (ref "P4") (pin "2") (pinfunction "2_2") (pintype "passive"))
      (node (ref "P5") (pin "2") (pinfunction "2_2") (pintype "passive"))
      (node (ref "P6") (pin "3") (pinfunction "3_3") (pintype "passive"))
      (node (ref "P6") (pin "4") (pinfunction "4_4") (pintype "passive"))
      (node (ref "Q1") (pin "2") (pinfunction "S_2") (pintype "passive"))
      (node (ref "R3") (pin "1") (pinfunction "1_1") (pintype "passive"))
      (node (ref "U1") (pin "1") (pinfunction "-Vin_1") (pintype "passive"))
      (node (ref "U4") (pin "3") (pinfunction "E_3") (pintype "passive"))
    )
    (net (code "23") (name "Net-(C1-Pad2)") (class "Default")
      (node (ref "C1") (pin "2") (pinfunction "2_2") (pintype "passive"))
      (node (ref "C2") (pin "2") (pinfunction "2_2") (pintype "passive"))
      (node (ref "L1") (pin "2") (pinfunction "2_2") (pintype "passive"))
      (node (ref "P2") (pin "2") (pinfunction "2_2") (pintype "passive"))
    )
    (net (code "24") (name "Net-(C11-Pad2)") (class "Default")
      (node (ref "C11") (pin "2") (pinfunction "2_2") (pintype "passive"))
      (node (ref "C5") (pin "1") (pinfunction "1_1") (pintype "passive"))
      (node (ref "L2") (pin "2") (pinfunction "2_2") (pintype "passive"))
      (node (ref "L3") (pin "1") (pinfunction "1_1") (pintype "passive"))
    )
    (net (code "25") (name "Net-(Green1-A)") (class "Default")
      (node (ref "Green1") (pin "1") (pinfunction "A_1") (pintype "passive"))
      (node (ref "R16") (pin "1") (pinfunction "1_1") (pintype "passive"))
    )
    (net (code "26") (name "Net-(M1-Video)") (class "Default")
      (node (ref "M1") (pin "10") (pinfunction "Video_10") (pintype "passive"))
      (node (ref "R4") (pin "2") (pinfunction "2_2") (pintype "passive"))
    )
    (net (code "27") (name "Net-(M2-IN+)") (class "Default")
      (node (ref "C15") (pin "1") (pinfunction "1_1") (pintype "passive"))
      (node (ref "C18") (pin "2") (pinfunction "2_2") (pintype "passive"))
      (node (ref "M2") (pin "0") (pinfunction "IN+_0") (pintype "passive"))
      (node (ref "P5") (pin "1") (pinfunction "1_1") (pintype "passive"))
    )
    (net (code "28") (name "Net-(P11-GND)") (class "Default")
      (node (ref "P11") (pin "1") (pinfunction "GND_1") (pintype "passive"))
      (node (ref "P12") (pin "4") (pinfunction "4_4") (pintype "passive"))
    )
    (net (code "29") (name "Net-(P11-SCL)") (class "Default")
      (node (ref "P11") (pin "3") (pinfunction "SCL_3") (pintype "passive"))
      (node (ref "P12") (pin "2") (pinfunction "2_2") (pintype "passive"))
    )
    (net (code "30") (name "Net-(P11-SDA)") (class "Default")
      (node (ref "P11") (pin "4") (pinfunction "SDA_4") (pintype "passive"))
      (node (ref "P12") (pin "1") (pinfunction "1_1") (pintype "passive"))
    )
    (net (code "31") (name "Net-(P11-VCC)") (class "Default")
      (node (ref "P11") (pin "2") (pinfunction "VCC_2") (pintype "passive"))
      (node (ref "P12") (pin "3") (pinfunction "3_3") (pintype "passive"))
    )
    (net (code "32") (name "Net-(Q1-D)") (class "Default")
      (node (ref "DS1") (pin "2") (pinfunction "2_2") (pintype "passive"))
      (node (ref "Q1") (pin "3") (pinfunction "D_3") (pintype "passive"))
    )
    (net (code "33") (name "Net-(Q1-G)") (class "Default")
      (node (ref "Q1") (pin "1") (pinfunction "G_1") (pintype "passive"))
      (node (ref "R1") (pin "1") (pinfunction "1_1") (pintype "passive"))
      (node (ref "R3") (pin "2") (pinfunction "2_2") (pintype "passive"))
      (node (ref "U4") (pin "4") (pinfunction "C_4") (pintype "passive"))
    )
    (net (code "34") (name "Net-(Q2-B)") (class "Default")
      (node (ref "Q2") (pin "1") (pinfunction "B_1") (pintype "passive"))
      (node (ref "R17") (pin "1") (pinfunction "1_1") (pintype "passive"))
    )
    (net (code "35") (name "Net-(Q3-B)") (class "Default")
      (node (ref "Q3") (pin "1") (pinfunction "B_1") (pintype "passive"))
      (node (ref "R18") (pin "1") (pinfunction "1_1") (pintype "passive"))
    )
    (net (code "36") (name "Net-(Red1-A)") (class "Default")
      (node (ref "R19") (pin "2") (pinfunction "2_2") (pintype "passive"))
      (node (ref "Red1") (pin "1") (pinfunction "A_1") (pintype "passive"))
    )
    (net (code "37") (name "Net-(S1-NO)") (class "Default")
      (node (ref "DS1") (pin "1") (pinfunction "1_1") (pintype "passive"))
      (node (ref "S1") (pin "2") (pinfunction "NO_2") (pintype "passive"))
    )
    (net (code "38") (name "Net-(U1-+Vout)") (class "Default")
      (node (ref "C3") (pin "1") (pinfunction "1_1") (pintype "passive"))
      (node (ref "C9") (pin "2") (pinfunction "2_2") (pintype "passive"))
      (node (ref "U1") (pin "6") (pinfunction "+Vout_6") (pintype "passive"))
      (node (ref "U2") (pin "2") (pinfunction "Vin_2") (pintype "passive"))
    )
    (net (code "39") (name "Net-(U1--Vout)") (class "Default")
      (node (ref "L5") (pin "1") (pinfunction "1_1") (pintype "passive"))
      (node (ref "U1") (pin "4") (pinfunction "-Vout_4") (pintype "passive"))
    )
    (net (code "40") (name "Net-(U2-Vout)") (class "Default")
      (node (ref "C10") (pin "2") (pinfunction "2_2") (pintype "passive"))
      (node (ref "C4") (pin "1") (pinfunction "1_1") (pintype "passive"))
      (node (ref "L2") (pin "1") (pinfunction "1_1") (pintype "passive"))
      (node (ref "U2") (pin "3") (pinfunction "Vout_3") (pintype "passive"))
    )
    (net (code "41") (name "Net-(U3-Vout)") (class "Default")
      (node (ref "C13") (pin "2") (pinfunction "2_2") (pintype "passive"))
      (node (ref "C7") (pin "1") (pinfunction "1_1") (pintype "passive"))
      (node (ref "L4") (pin "1") (pinfunction "1_1") (pintype "passive"))
      (node (ref "U3") (pin "3") (pinfunction "Vout_3") (pintype "passive"))
    )
    (net (code "42") (name "Net-(U4-A)") (class "Default")
      (node (ref "R2") (pin "1") (pinfunction "1_1") (pintype "passive"))
      (node (ref "U4") (pin "1") (pinfunction "A_1") (pintype "passive"))
    )
    (net (code "43") (name "Net-(U5A-+)") (class "Default")
      (node (ref "R4") (pin "1") (pinfunction "1_1") (pintype "passive"))
      (node (ref "R5") (pin "2") (pinfunction "2_2") (pintype "passive"))
      (node (ref "U5") (pin "3") (pinfunction "+_3") (pintype "passive"))
    )
    (net (code "44") (name "Net-(U5A--)") (class "Default")
      (node (ref "R6") (pin "2") (pinfunction "2_2") (pintype "passive"))
      (node (ref "Rf1") (pin "1") (pinfunction "1_1") (pintype "passive"))
      (node (ref "U5") (pin "2") (pinfunction "-_2") (pintype "passive"))
    )
    (net (code "45") (name "Net-(U6-EN)") (class "Default")
      (node (ref "R9") (pin "2") (pinfunction "2_2") (pintype "passive"))
      (node (ref "U6") (pin "3") (pinfunction "EN_3") (pintype "passive"))
    )
    (net (code "46") (name "Net-(U6-RXD0)") (class "Default")
      (node (ref "R8") (pin "1") (pinfunction "1_1") (pintype "passive"))
      (node (ref "U6") (pin "21") (pinfunction "RXD0_21") (pintype "passive"))
    )
    (net (code "47") (name "Net-(U6-TXD0)") (class "Default")
      (node (ref "R7") (pin "1") (pinfunction "1_1") (pintype "passive"))
      (node (ref "U6") (pin "22") (pinfunction "TXD0_22") (pintype "passive"))
    )
    (net (code "48") (name "unconnected-(M1-EOS-Pad7)") (class "Default")
      (node (ref "M1") (pin "7") (pinfunction "EOS_7") (pintype "passive"))
    )
    (net (code "49") (name "unconnected-(M1-Gain-Pad6)") (class "Default")
      (node (ref "M1") (pin "6") (pinfunction "Gain_6") (pintype "passive"))
    )
    (net (code "50") (name "unconnected-(M1-NC-Pad3)") (class "Default")
      (node (ref "M1") (pin "3") (pinfunction "NC_3") (pintype "passive"))
    )
    (net (code "51") (name "unconnected-(M1-NC-Pad5)") (class "Default")
      (node (ref "M1") (pin "5") (pinfunction "NC_5") (pintype "passive"))
    )
    (net (code "52") (name "unconnected-(M1-NC-Pad8)") (class "Default")
      (node (ref "M1") (pin "8") (pinfunction "NC_8") (pintype "passive"))
    )
    (net (code "53") (name "unconnected-(P13-ID-Pad4)") (class "Default")
      (node (ref "P13") (pin "4") (pinfunction "ID_4") (pintype "passive"))
    )
    (net (code "54") (name "unconnected-(U6-CS0-Pad9)") (class "Default")
      (node (ref "U6") (pin "9") (pinfunction "CS0_9") (pintype "passive"))
    )
    (net (code "55") (name "unconnected-(U6-GPIO9-Pad11)") (class "Default")
      (node (ref "U6") (pin "11") (pinfunction "GPIO9_11") (pintype "passive"))
    )
    (net (code "56") (name "unconnected-(U6-GPIO10-Pad12)") (class "Default")
      (node (ref "U6") (pin "12") (pinfunction "GPIO10_12") (pintype "passive"))
    )
    (net (code "57") (name "unconnected-(U6-GPIO12-Pad6)") (class "Default")
      (node (ref "U6") (pin "6") (pinfunction "GPIO12_6") (pintype "passive"))
    )
    (net (code "58") (name "unconnected-(U6-GPIO16-Pad4)") (class "Default")
      (node (ref "U6") (pin "4") (pinfunction "GPIO16_4") (pintype "passive"))
    )
    (net (code "59") (name "unconnected-(U6-MISO-Pad10)") (class "Default")
      (node (ref "U6") (pin "10") (pinfunction "MISO_10") (pintype "passive"))
    )
    (net (code "60") (name "unconnected-(U6-MOSI-Pad13)") (class "Default")
      (node (ref "U6") (pin "13") (pinfunction "MOSI_13") (pintype "passive"))
    )
    (net (code "61") (name "unconnected-(U6-SCLK-Pad14)") (class "Default")
      (node (ref "U6") (pin "14") (pinfunction "SCLK_14") (pintype "passive"))
    )
    (net (code "62") (name "unconnected-(U7-RTS#-Pad4)") (class "Default")
      (node (ref "U7") (pin "4") (pinfunction "RTS#_4") (pintype "passive"))
    )
  )
)
